# Sensor_Board.net
KiCad netlist of a schematic drawn in EAGLE
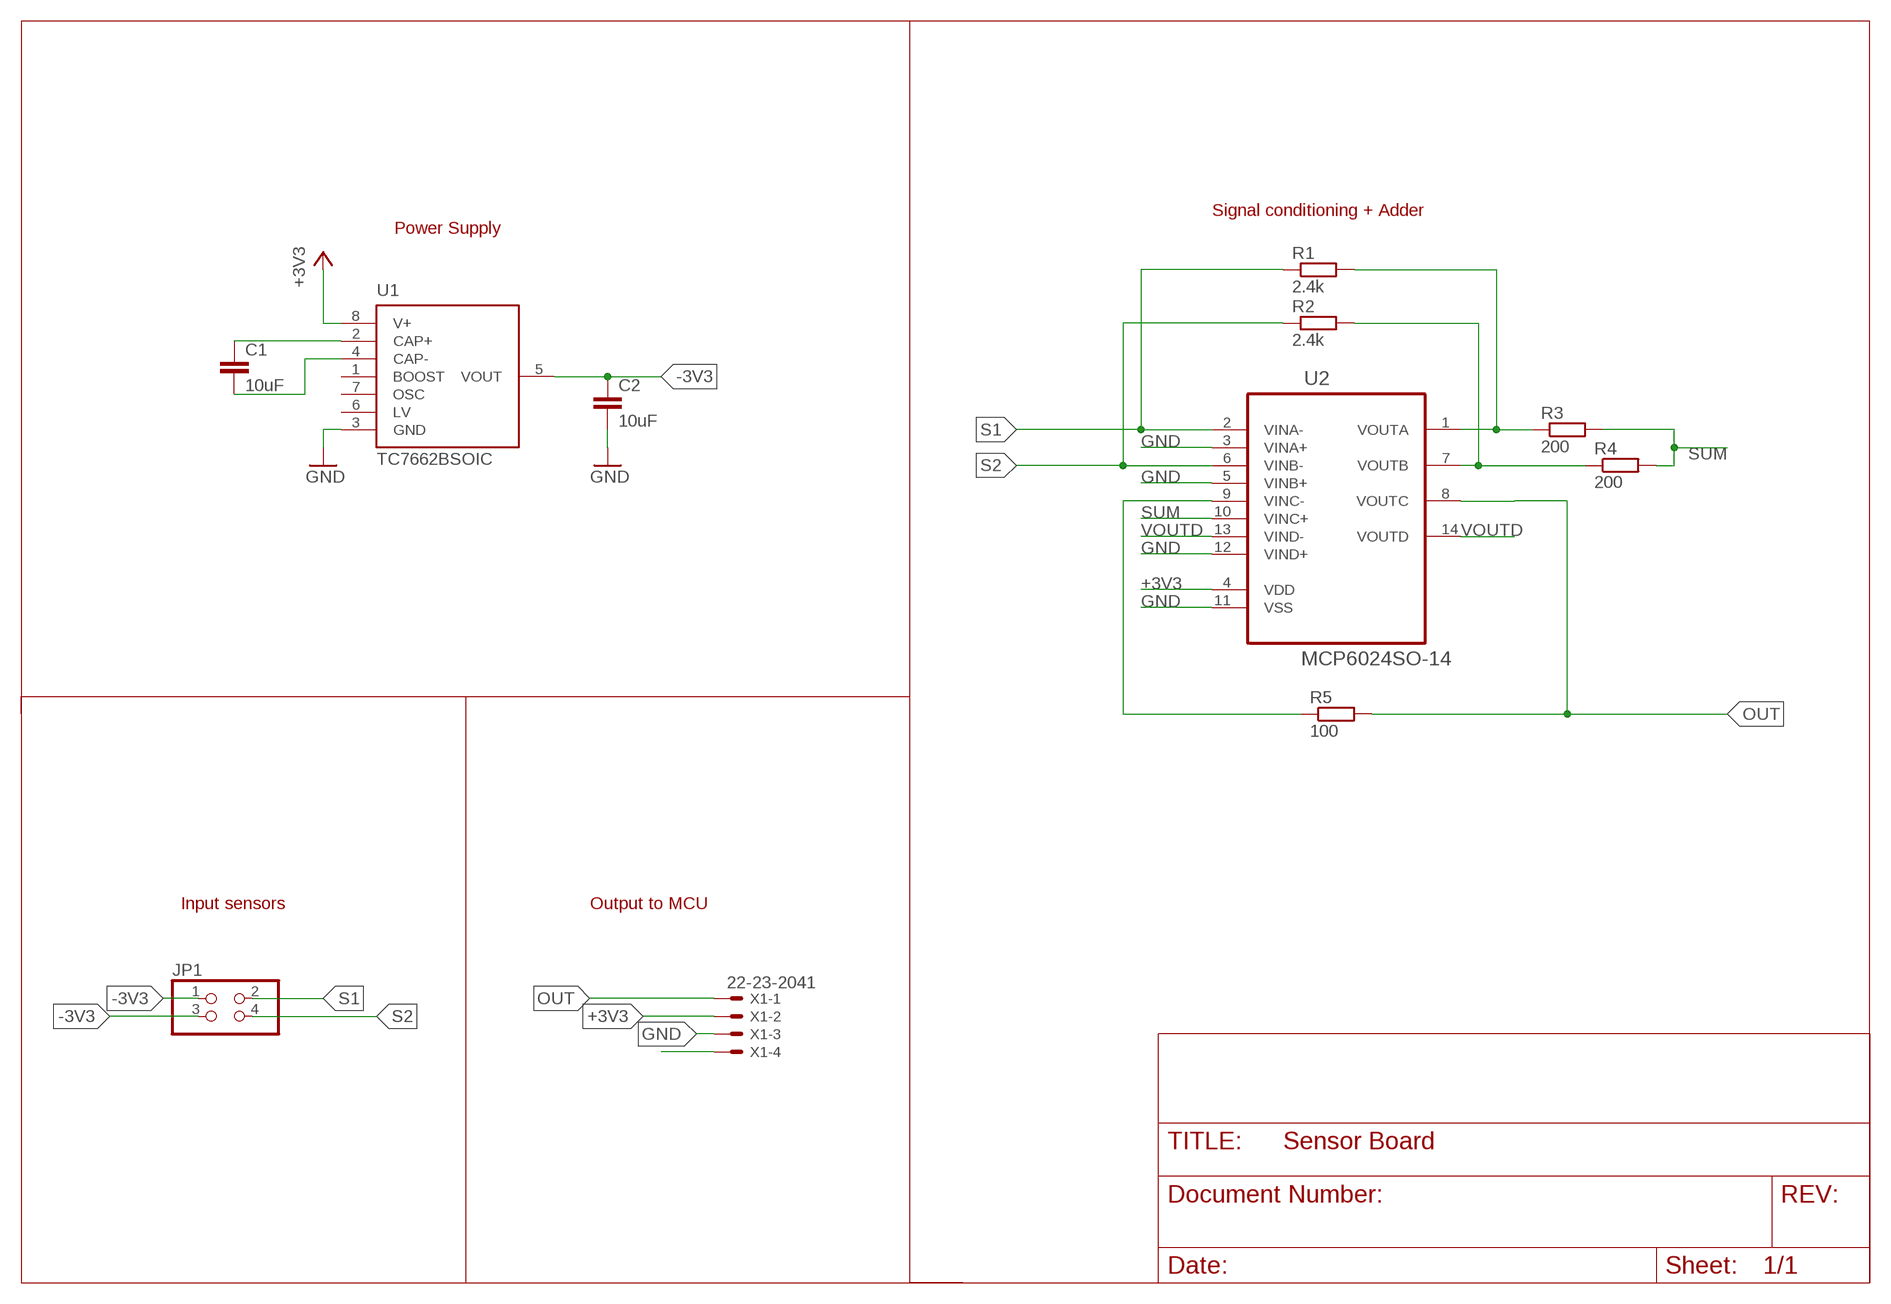
[diagram p0: schematic, sheet 1]

(export (version "E")
  (design (tool "Eeschema 10.0.6"))
  (components
    (comp (ref "C1")
      (value "10uF")
      (footprint "eagle-import:C0603")
      (libsource (lib "eagle-import") (part "C-EUC0603"))
    )
    (comp (ref "C2")
      (value "10uF")
      (footprint "eagle-import:C0603")
      (libsource (lib "eagle-import") (part "C-EUC0603"))
    )
    (comp (ref "JP1")
      (value "PINHD-2X2/90")
      (footprint "eagle-import:2X02_90")
      (libsource (lib "eagle-import") (part "PINHD-2X2/90"))
    )
    (comp (ref "R1")
      (value "2.4k")
      (footprint "eagle-import:R0603")
      (libsource (lib "eagle-import") (part "R-EU_R0603"))
    )
    (comp (ref "R2")
      (value "2.4k")
      (footprint "eagle-import:R0603")
      (libsource (lib "eagle-import") (part "R-EU_R0603"))
    )
    (comp (ref "R3")
      (value "200")
      (footprint "eagle-import:R0603")
      (libsource (lib "eagle-import") (part "R-EU_R0603"))
    )
    (comp (ref "R4")
      (value "200")
      (footprint "eagle-import:R0603")
      (libsource (lib "eagle-import") (part "R-EU_R0603"))
    )
    (comp (ref "R5")
      (value "100")
      (footprint "eagle-import:R0603")
      (libsource (lib "eagle-import") (part "R-EU_R0603"))
    )
    (comp (ref "U1")
      (value "TC7662BSOIC")
      (footprint "eagle-import:SO-08")
      (fields (field (name "SPICEPREFIX") "X"))
      (libsource (lib "eagle-import") (part "TC7662BSOIC"))
    )
    (comp (ref "U2")
      (value "MCP6024SO-14")
      (footprint "eagle-import:SO-14")
      (libsource (lib "eagle-import") (part "MCP6024SO-14"))
    )
    (comp (ref "X1")
      (value "22-23-2041")
      (footprint "eagle-import:22-23-2041")
      (fields (field (name "MF") "MOLEX"))
      (libsource (lib "eagle-import") (part "22-23-2041"))
    )
  )
  (nets
    (net (code "1") (name "+3V3") (class "Default")
      (node (ref "U1") (pin "8") (pinfunction "V+_8") (pintype "power_in"))
      (node (ref "U2") (pin "4") (pinfunction "VDD_4") (pintype "power_in"))
      (node (ref "X1") (pin "2") (pinfunction "S_2") (pintype "passive"))
    )
    (net (code "2") (name "-3V3") (class "Default")
      (node (ref "C2") (pin "1") (pinfunction "1_1") (pintype "passive"))
      (node (ref "JP1") (pin "1") (pinfunction "1_1") (pintype "passive"))
      (node (ref "JP1") (pin "3") (pinfunction "3_3") (pintype "passive"))
      (node (ref "U1") (pin "5") (pinfunction "VOUT_5") (pintype "output"))
    )
    (net (code "3") (name "/SUM") (class "Default")
      (node (ref "R3") (pin "2") (pinfunction "2_2") (pintype "passive"))
      (node (ref "R4") (pin "2") (pinfunction "2_2") (pintype "passive"))
      (node (ref "U2") (pin "10") (pinfunction "VINC+_10") (pintype "input"))
    )
    (net (code "4") (name "/VOUTD") (class "Default")
      (node (ref "U2") (pin "13") (pinfunction "VIND-_13") (pintype "input"))
      (node (ref "U2") (pin "14") (pinfunction "VOUTD_14") (pintype "output"))
    )
    (net (code "5") (name "GND") (class "Default")
      (node (ref "C2") (pin "2") (pinfunction "2_2") (pintype "passive"))
      (node (ref "U1") (pin "3") (pinfunction "GND_3") (pintype "power_in"))
      (node (ref "U2") (pin "11") (pinfunction "VSS_11") (pintype "passive"))
      (node (ref "U2") (pin "12") (pinfunction "VIND+_12") (pintype "input"))
      (node (ref "U2") (pin "3") (pinfunction "VINA+_3") (pintype "input"))
      (node (ref "U2") (pin "5") (pinfunction "VINB+_5") (pintype "input"))
      (node (ref "X1") (pin "3") (pinfunction "S_3") (pintype "passive"))
    )
    (net (code "6") (name "Net-(U1-CAP+)") (class "Default")
      (node (ref "C1") (pin "1") (pinfunction "1_1") (pintype "passive"))
      (node (ref "U1") (pin "2") (pinfunction "CAP+_2") (pintype "input"))
    )
    (net (code "7") (name "Net-(U1-CAP-)") (class "Default")
      (node (ref "C1") (pin "2") (pinfunction "2_2") (pintype "passive"))
      (node (ref "U1") (pin "4") (pinfunction "CAP-_4") (pintype "input"))
    )
    (net (code "8") (name "Net-(U2-VINC-)") (class "Default")
      (node (ref "R5") (pin "1") (pinfunction "1_1") (pintype "passive"))
      (node (ref "U2") (pin "9") (pinfunction "VINC-_9") (pintype "input"))
    )
    (net (code "9") (name "Net-(U2-VOUTA)") (class "Default")
      (node (ref "R1") (pin "2") (pinfunction "2_2") (pintype "passive"))
      (node (ref "R3") (pin "1") (pinfunction "1_1") (pintype "passive"))
      (node (ref "U2") (pin "1") (pinfunction "VOUTA_1") (pintype "output"))
    )
    (net (code "10") (name "Net-(U2-VOUTB)") (class "Default")
      (node (ref "R2") (pin "2") (pinfunction "2_2") (pintype "passive"))
      (node (ref "R4") (pin "1") (pinfunction "1_1") (pintype "passive"))
      (node (ref "U2") (pin "7") (pinfunction "VOUTB_7") (pintype "output"))
    )
    (net (code "11") (name "OUT") (class "Default")
      (node (ref "R5") (pin "2") (pinfunction "2_2") (pintype "passive"))
      (node (ref "U2") (pin "8") (pinfunction "VOUTC_8") (pintype "output"))
      (node (ref "X1") (pin "1") (pinfunction "S_1") (pintype "passive"))
    )
    (net (code "12") (name "S1") (class "Default")
      (node (ref "JP1") (pin "2") (pinfunction "2_2") (pintype "passive"))
      (node (ref "R1") (pin "1") (pinfunction "1_1") (pintype "passive"))
      (node (ref "U2") (pin "2") (pinfunction "VINA-_2") (pintype "input"))
    )
    (net (code "13") (name "S2") (class "Default")
      (node (ref "JP1") (pin "4") (pinfunction "4_4") (pintype "passive"))
      (node (ref "R2") (pin "1") (pinfunction "1_1") (pintype "passive"))
      (node (ref "U2") (pin "6") (pinfunction "VINB-_6") (pintype "input"))
    )
    (net (code "14") (name "unconnected-(U1-BOOST-Pad1)") (class "Default")
      (node (ref "U1") (pin "1") (pinfunction "BOOST_1") (pintype "input"))
    )
    (net (code "15") (name "unconnected-(U1-LV-Pad6)") (class "Default")
      (node (ref "U1") (pin "6") (pinfunction "LV_6") (pintype "input"))
    )
    (net (code "16") (name "unconnected-(U1-OSC-Pad7)") (class "Default")
      (node (ref "U1") (pin "7") (pinfunction "OSC_7") (pintype "input"))
    )
    (net (code "17") (name "unconnected-(X1D-S-Pad4)") (class "Default")
      (node (ref "X1") (pin "4") (pinfunction "S_4") (pintype "passive"))
    )
  )
)
